# Dip_Switch.net
KiCad netlist of a schematic drawn in Altium Designer
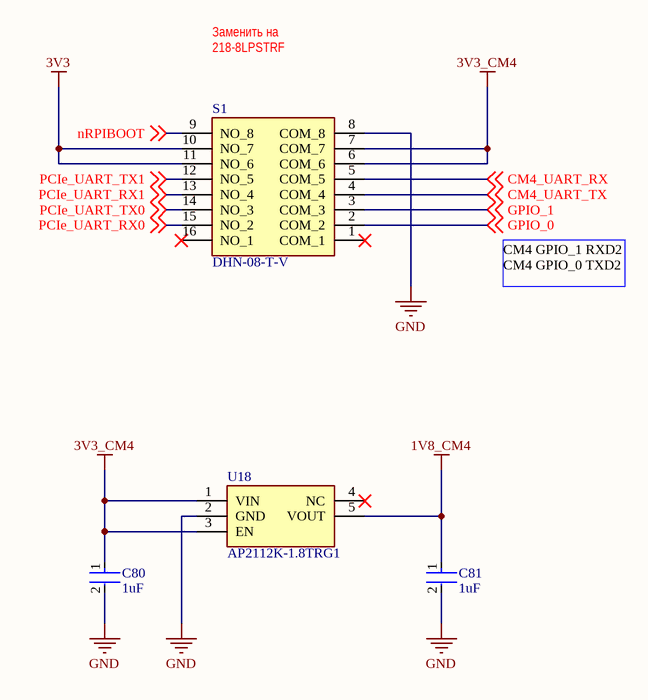
[diagram p0: Dip_Switch.SchDoc]

(export (version "E")
  (design (tool "Eeschema 10.0.6"))
  (components
    (comp (ref "C80")
      (value "1uF")
      (footprint "FP-CC0805-0_85-MFG")
      (description "CAP CER 1UF 10V X7R 0805")
      (fields
        (field (name "MANUFACTURER") "Yageo")
        (field (name "OCTOPART") "https://octopart.com/cc0805kkx7r6bb105-yageo-42522859")
      )
      (libsource (lib "Altium Content Vault") (part "11868f565c42a9108669ba33697ecf6"))
    )
    (comp (ref "C81")
      (value "1uF")
      (footprint "FP-CC0805-0_85-MFG")
      (description "CAP CER 1UF 10V X7R 0805")
      (fields
        (field (name "MANUFACTURER") "Yageo")
        (field (name "OCTOPART") "https://octopart.com/cc0805kkx7r6bb105-yageo-42522859")
      )
      (libsource (lib "Altium Content Vault") (part "11868f565c42a9108669ba33697ecf6"))
    )
    (comp (ref "S1")
      (value "DHN-08-T-V")
      (footprint "SamacSys:DHN08TV")
      (description "Switch")
      (fields (field (name "MOUSER PART NUMBER") "113-DHN-08-T-V"))
      (libsource (lib "*") (part "DHN-08-T-V"))
    )
    (comp (ref "U18")
      (value "AP2112K-1.8TRG1")
      (footprint "SamacSys:SOT95P285X140-5N")
      (description "Integrated Circuit")
      (fields (field (name "MOUSER PART NUMBER") "621-AP2112K-1.8TRG1"))
      (libsource (lib "*") (part "AP2112K-1.8TRG1"))
    )
  )
  (nets
    (net (code "1") (name "1V8_CM4") (class "Default")
      (node (ref "C81") (pin "1") (pinfunction "1_1") (pintype "passive"))
      (node (ref "U18") (pin "5") (pinfunction "VOUT_5") (pintype "passive"))
    )
    (net (code "2") (name "3V3") (class "Default")
      (node (ref "S1") (pin "10") (pinfunction "NO_7_10") (pintype "passive"))
      (node (ref "S1") (pin "11") (pinfunction "NO_6_11") (pintype "passive"))
    )
    (net (code "3") (name "3V3_CM4") (class "Default")
      (node (ref "C80") (pin "1") (pinfunction "1_1") (pintype "passive"))
      (node (ref "S1") (pin "6") (pinfunction "COM_6_6") (pintype "passive"))
      (node (ref "S1") (pin "7") (pinfunction "COM_7_7") (pintype "passive"))
      (node (ref "U18") (pin "1") (pinfunction "VIN_1") (pintype "passive"))
      (node (ref "U18") (pin "3") (pinfunction "EN_3") (pintype "passive"))
    )
    (net (code "4") (name "CM4_UART_RX") (class "Default")
      (node (ref "S1") (pin "5") (pinfunction "COM_5_5") (pintype "passive"))
    )
    (net (code "5") (name "CM4_UART_TX") (class "Default")
      (node (ref "S1") (pin "4") (pinfunction "COM_4_4") (pintype "passive"))
    )
    (net (code "6") (name "GND") (class "Default")
      (node (ref "C80") (pin "2") (pinfunction "2_2") (pintype "passive"))
      (node (ref "C81") (pin "2") (pinfunction "2_2") (pintype "passive"))
      (node (ref "S1") (pin "8") (pinfunction "COM_8_8") (pintype "passive"))
      (node (ref "U18") (pin "2") (pinfunction "GND_2") (pintype "passive"))
    )
    (net (code "7") (name "GPIO_0") (class "Default")
      (node (ref "S1") (pin "2") (pinfunction "COM_2_2") (pintype "passive"))
    )
    (net (code "8") (name "GPIO_1") (class "Default")
      (node (ref "S1") (pin "3") (pinfunction "COM_3_3") (pintype "passive"))
    )
    (net (code "9") (name "PCIe_UART_RX0") (class "Default")
      (node (ref "S1") (pin "15") (pinfunction "NO_2_15") (pintype "passive"))
    )
    (net (code "10") (name "PCIe_UART_RX1") (class "Default")
      (node (ref "S1") (pin "13") (pinfunction "NO_4_13") (pintype "passive"))
    )
    (net (code "11") (name "PCIe_UART_TX0") (class "Default")
      (node (ref "S1") (pin "14") (pinfunction "NO_3_14") (pintype "passive"))
    )
    (net (code "12") (name "PCIe_UART_TX1") (class "Default")
      (node (ref "S1") (pin "12") (pinfunction "NO_5_12") (pintype "passive"))
    )
    (net (code "13") (name "nRPIBOOT") (class "Default")
      (node (ref "S1") (pin "9") (pinfunction "NO_8_9") (pintype "passive"))
    )
    (net (code "14") (name "unconnected-(S1-COM_1-Pad1)") (class "Default")
      (node (ref "S1") (pin "1") (pinfunction "COM_1_1") (pintype "passive+no_connect"))
    )
    (net (code "15") (name "unconnected-(S1-NO_1-Pad16)") (class "Default")
      (node (ref "S1") (pin "16") (pinfunction "NO_1_16") (pintype "passive+no_connect"))
    )
    (net (code "16") (name "unconnected-(U18-NC-Pad4)") (class "Default")
      (node (ref "U18") (pin "4") (pinfunction "NC_4") (pintype "passive+no_connect"))
    )
  )
)
